# ftdi_breakout.net
KiCad netlist of a schematic drawn in EAGLE
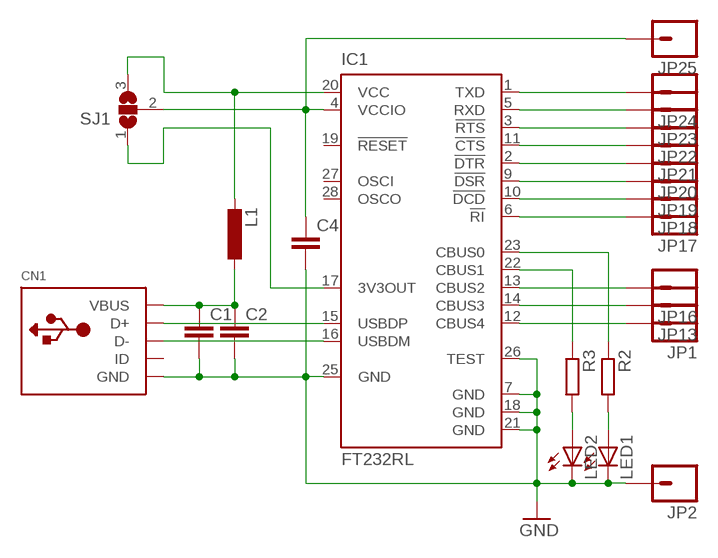
[diagram p0: schematic, sheet 1]

(export (version "E")
  (design (tool "Eeschema 10.0.6"))
  (components
    (comp (ref "C1")
      (value "C-EUC1206K")
      (footprint "eagle-import:C1206K")
      (libsource (lib "eagle-import") (part "C-EUC1206K"))
    )
    (comp (ref "C2")
      (value "C-EUC1206K")
      (footprint "eagle-import:C1206K")
      (libsource (lib "eagle-import") (part "C-EUC1206K"))
    )
    (comp (ref "C4")
      (value "C-EUC1206K")
      (footprint "eagle-import:C1206K")
      (libsource (lib "eagle-import") (part "C-EUC1206K"))
    )
    (comp (ref "CN1")
      (value "USBMINIB")
      (footprint "eagle-import:USB-MINIB")
      (libsource (lib "eagle-import") (part "USBMINIB"))
    )
    (comp (ref "IC1")
      (value "FT232RL")
      (footprint "eagle-import:SSOP28")
      (libsource (lib "eagle-import") (part "FT232RL"))
    )
    (comp (ref "JP1")
      (value "M01PTH_LONGPAD")
      (footprint "eagle-import:1X01_LONGPAD")
      (libsource (lib "eagle-import") (part "M01PTH_LONGPAD"))
    )
    (comp (ref "JP2")
      (value "M01PTH_LONGPAD")
      (footprint "eagle-import:1X01_LONGPAD")
      (libsource (lib "eagle-import") (part "M01PTH_LONGPAD"))
    )
    (comp (ref "JP13")
      (value "M01PTH_LONGPAD")
      (footprint "eagle-import:1X01_LONGPAD")
      (libsource (lib "eagle-import") (part "M01PTH_LONGPAD"))
    )
    (comp (ref "JP16")
      (value "M01PTH_LONGPAD")
      (footprint "eagle-import:1X01_LONGPAD")
      (libsource (lib "eagle-import") (part "M01PTH_LONGPAD"))
    )
    (comp (ref "JP17")
      (value "M01PTH_LONGPAD")
      (footprint "eagle-import:1X01_LONGPAD")
      (libsource (lib "eagle-import") (part "M01PTH_LONGPAD"))
    )
    (comp (ref "JP18")
      (value "M01PTH_LONGPAD")
      (footprint "eagle-import:1X01_LONGPAD")
      (libsource (lib "eagle-import") (part "M01PTH_LONGPAD"))
    )
    (comp (ref "JP19")
      (value "M01PTH_LONGPAD")
      (footprint "eagle-import:1X01_LONGPAD")
      (libsource (lib "eagle-import") (part "M01PTH_LONGPAD"))
    )
    (comp (ref "JP20")
      (value "M01PTH_LONGPAD")
      (footprint "eagle-import:1X01_LONGPAD")
      (libsource (lib "eagle-import") (part "M01PTH_LONGPAD"))
    )
    (comp (ref "JP21")
      (value "M01PTH_LONGPAD")
      (footprint "eagle-import:1X01_LONGPAD")
      (libsource (lib "eagle-import") (part "M01PTH_LONGPAD"))
    )
    (comp (ref "JP22")
      (value "M01PTH_LONGPAD")
      (footprint "eagle-import:1X01_LONGPAD")
      (libsource (lib "eagle-import") (part "M01PTH_LONGPAD"))
    )
    (comp (ref "JP23")
      (value "M01PTH_LONGPAD")
      (footprint "eagle-import:1X01_LONGPAD")
      (libsource (lib "eagle-import") (part "M01PTH_LONGPAD"))
    )
    (comp (ref "JP24")
      (value "M01PTH_LONGPAD")
      (footprint "eagle-import:1X01_LONGPAD")
      (libsource (lib "eagle-import") (part "M01PTH_LONGPAD"))
    )
    (comp (ref "JP25")
      (value "M01PTH_LONGPAD")
      (footprint "eagle-import:1X01_LONGPAD")
      (libsource (lib "eagle-import") (part "M01PTH_LONGPAD"))
    )
    (comp (ref "L1")
      (value "L-EUL2825P")
      (footprint "eagle-import:L2825P")
      (libsource (lib "eagle-import") (part "L-EUL2825P"))
    )
    (comp (ref "LED1")
      (value "LEDCHIPLED_0805")
      (footprint "eagle-import:CHIPLED_0805")
      (libsource (lib "eagle-import") (part "LEDCHIPLED_0805"))
    )
    (comp (ref "LED2")
      (value "LEDCHIPLED_0805")
      (footprint "eagle-import:CHIPLED_0805")
      (libsource (lib "eagle-import") (part "LEDCHIPLED_0805"))
    )
    (comp (ref "R2")
      (value "R-EU_M0805")
      (footprint "eagle-import:M0805")
      (libsource (lib "eagle-import") (part "R-EU_M0805"))
    )
    (comp (ref "R3")
      (value "R-EU_R0805")
      (footprint "eagle-import:R0805")
      (libsource (lib "eagle-import") (part "R-EU_R0805"))
    )
    (comp (ref "SJ1")
      (value "SJ2W")
      (footprint "eagle-import:SJ_2")
      (libsource (lib "eagle-import") (part "SJ2W"))
    )
  )
  (nets
    (net (code "1") (name "GND") (class "Default")
      (node (ref "C1") (pin "2") (pinfunction "2_2") (pintype "passive"))
      (node (ref "C2") (pin "2") (pinfunction "2_2") (pintype "passive"))
      (node (ref "C4") (pin "2") (pinfunction "2_2") (pintype "passive"))
      (node (ref "CN1") (pin "GND") (pinfunction "GND_GND") (pintype "power_in"))
      (node (ref "IC1") (pin "18") (pinfunction "GND_18") (pintype "power_in"))
      (node (ref "IC1") (pin "21") (pinfunction "GND_21") (pintype "power_in"))
      (node (ref "IC1") (pin "25") (pinfunction "GND_25") (pintype "power_in"))
      (node (ref "IC1") (pin "26") (pinfunction "TEST_26") (pintype "input"))
      (node (ref "IC1") (pin "7") (pinfunction "GND_7") (pintype "power_in"))
      (node (ref "JP2") (pin "1") (pinfunction "1_1") (pintype "passive"))
      (node (ref "LED1") (pin "C") (pinfunction "C_C") (pintype "passive"))
      (node (ref "LED2") (pin "C") (pinfunction "C_C") (pintype "passive"))
    )
    (net (code "2") (name "Net-(C1-Pad1)") (class "Default")
      (node (ref "C1") (pin "1") (pinfunction "1_1") (pintype "passive"))
      (node (ref "C2") (pin "1") (pinfunction "1_1") (pintype "passive"))
      (node (ref "CN1") (pin "VBUS") (pinfunction "VBUS_VBUS") (pintype "power_in"))
      (node (ref "L1") (pin "1") (pinfunction "1_1") (pintype "passive"))
    )
    (net (code "3") (name "Net-(IC1-3V3OUT)") (class "Default")
      (node (ref "IC1") (pin "17") (pinfunction "3V3OUT_17") (pintype "output"))
      (node (ref "SJ1") (pin "1") (pinfunction "1_1") (pintype "passive"))
    )
    (net (code "4") (name "Net-(IC1-CBUS0)") (class "Default")
      (node (ref "IC1") (pin "23") (pinfunction "CBUS0_23") (pintype "bidirectional"))
      (node (ref "R2") (pin "1") (pinfunction "1_1") (pintype "passive"))
    )
    (net (code "5") (name "Net-(IC1-CBUS1)") (class "Default")
      (node (ref "IC1") (pin "22") (pinfunction "CBUS1_22") (pintype "bidirectional"))
      (node (ref "R3") (pin "1") (pinfunction "1_1") (pintype "passive"))
    )
    (net (code "6") (name "Net-(IC1-CBUS2)") (class "Default")
      (node (ref "IC1") (pin "13") (pinfunction "CBUS2_13") (pintype "bidirectional"))
      (node (ref "JP16") (pin "1") (pinfunction "1_1") (pintype "passive"))
    )
    (net (code "7") (name "Net-(IC1-CBUS3)") (class "Default")
      (node (ref "IC1") (pin "14") (pinfunction "CBUS3_14") (pintype "bidirectional"))
      (node (ref "JP13") (pin "1") (pinfunction "1_1") (pintype "passive"))
    )
    (net (code "8") (name "Net-(IC1-CBUS4)") (class "Default")
      (node (ref "IC1") (pin "12") (pinfunction "CBUS4_12") (pintype "bidirectional"))
      (node (ref "JP1") (pin "1") (pinfunction "1_1") (pintype "passive"))
    )
    (net (code "9") (name "Net-(IC1-RXD)") (class "Default")
      (node (ref "IC1") (pin "5") (pinfunction "RXD_5") (pintype "input"))
      (node (ref "JP23") (pin "1") (pinfunction "1_1") (pintype "passive"))
    )
    (net (code "10") (name "Net-(IC1-TXD)") (class "Default")
      (node (ref "IC1") (pin "1") (pinfunction "TXD_1") (pintype "output"))
      (node (ref "JP24") (pin "1") (pinfunction "1_1") (pintype "passive"))
    )
    (net (code "11") (name "Net-(IC1-USBDM)") (class "Default")
      (node (ref "CN1") (pin "D-") (pinfunction "D-_D-") (pintype "bidirectional"))
      (node (ref "IC1") (pin "16") (pinfunction "USBDM_16") (pintype "bidirectional"))
    )
    (net (code "12") (name "Net-(IC1-USBDP)") (class "Default")
      (node (ref "CN1") (pin "D+") (pinfunction "D+_D+") (pintype "bidirectional"))
      (node (ref "IC1") (pin "15") (pinfunction "USBDP_15") (pintype "bidirectional"))
    )
    (net (code "13") (name "Net-(IC1-VCC)") (class "Default")
      (node (ref "IC1") (pin "20") (pinfunction "VCC_20") (pintype "power_in"))
      (node (ref "L1") (pin "2") (pinfunction "2_2") (pintype "passive"))
      (node (ref "SJ1") (pin "3") (pinfunction "3_3") (pintype "passive"))
    )
    (net (code "14") (name "Net-(IC1-VCCIO)") (class "Default")
      (node (ref "C4") (pin "1") (pinfunction "1_1") (pintype "passive"))
      (node (ref "IC1") (pin "4") (pinfunction "VCCIO_4") (pintype "power_in"))
      (node (ref "JP25") (pin "1") (pinfunction "1_1") (pintype "passive"))
      (node (ref "SJ1") (pin "2") (pinfunction "2_2") (pintype "passive"))
    )
    (net (code "15") (name "Net-(IC1-~{CTS})") (class "Default")
      (node (ref "IC1") (pin "11") (pinfunction "~{CTS}_11") (pintype "input"))
      (node (ref "JP21") (pin "1") (pinfunction "1_1") (pintype "passive"))
    )
    (net (code "16") (name "Net-(IC1-~{DCD})") (class "Default")
      (node (ref "IC1") (pin "10") (pinfunction "~{DCD}_10") (pintype "input"))
      (node (ref "JP18") (pin "1") (pinfunction "1_1") (pintype "passive"))
    )
    (net (code "17") (name "Net-(IC1-~{DSR})") (class "Default")
      (node (ref "IC1") (pin "9") (pinfunction "~{DSR}_9") (pintype "input"))
      (node (ref "JP19") (pin "1") (pinfunction "1_1") (pintype "passive"))
    )
    (net (code "18") (name "Net-(IC1-~{DTR})") (class "Default")
      (node (ref "IC1") (pin "2") (pinfunction "~{DTR}_2") (pintype "output"))
      (node (ref "JP20") (pin "1") (pinfunction "1_1") (pintype "passive"))
    )
    (net (code "19") (name "Net-(IC1-~{RI})") (class "Default")
      (node (ref "IC1") (pin "6") (pinfunction "~{RI}_6") (pintype "input"))
      (node (ref "JP17") (pin "1") (pinfunction "1_1") (pintype "passive"))
    )
    (net (code "20") (name "Net-(IC1-~{RTS})") (class "Default")
      (node (ref "IC1") (pin "3") (pinfunction "~{RTS}_3") (pintype "output"))
      (node (ref "JP22") (pin "1") (pinfunction "1_1") (pintype "passive"))
    )
    (net (code "21") (name "Net-(LED1-PadA)") (class "Default")
      (node (ref "LED1") (pin "A") (pinfunction "A_A") (pintype "passive"))
      (node (ref "R2") (pin "2") (pinfunction "2_2") (pintype "passive"))
    )
    (net (code "22") (name "Net-(LED2-PadA)") (class "Default")
      (node (ref "LED2") (pin "A") (pinfunction "A_A") (pintype "passive"))
      (node (ref "R3") (pin "2") (pinfunction "2_2") (pintype "passive"))
    )
    (net (code "23") (name "unconnected-(CN1-PadID)") (class "Default")
      (node (ref "CN1") (pin "ID") (pinfunction "ID_ID") (pintype "bidirectional"))
    )
    (net (code "24") (name "unconnected-(IC1-OSCI-Pad27)") (class "Default")
      (node (ref "IC1") (pin "27") (pinfunction "OSCI_27") (pintype "input"))
    )
    (net (code "25") (name "unconnected-(IC1-OSCO-Pad28)") (class "Default")
      (node (ref "IC1") (pin "28") (pinfunction "OSCO_28") (pintype "output"))
    )
    (net (code "26") (name "unconnected-(IC1-~{RESET}-Pad19)") (class "Default")
      (node (ref "IC1") (pin "19") (pinfunction "~{RESET}_19") (pintype "input"))
    )
  )
)
